# instaspin_bldc_driver.net
KiCad netlist of a schematic drawn in Altium Designer
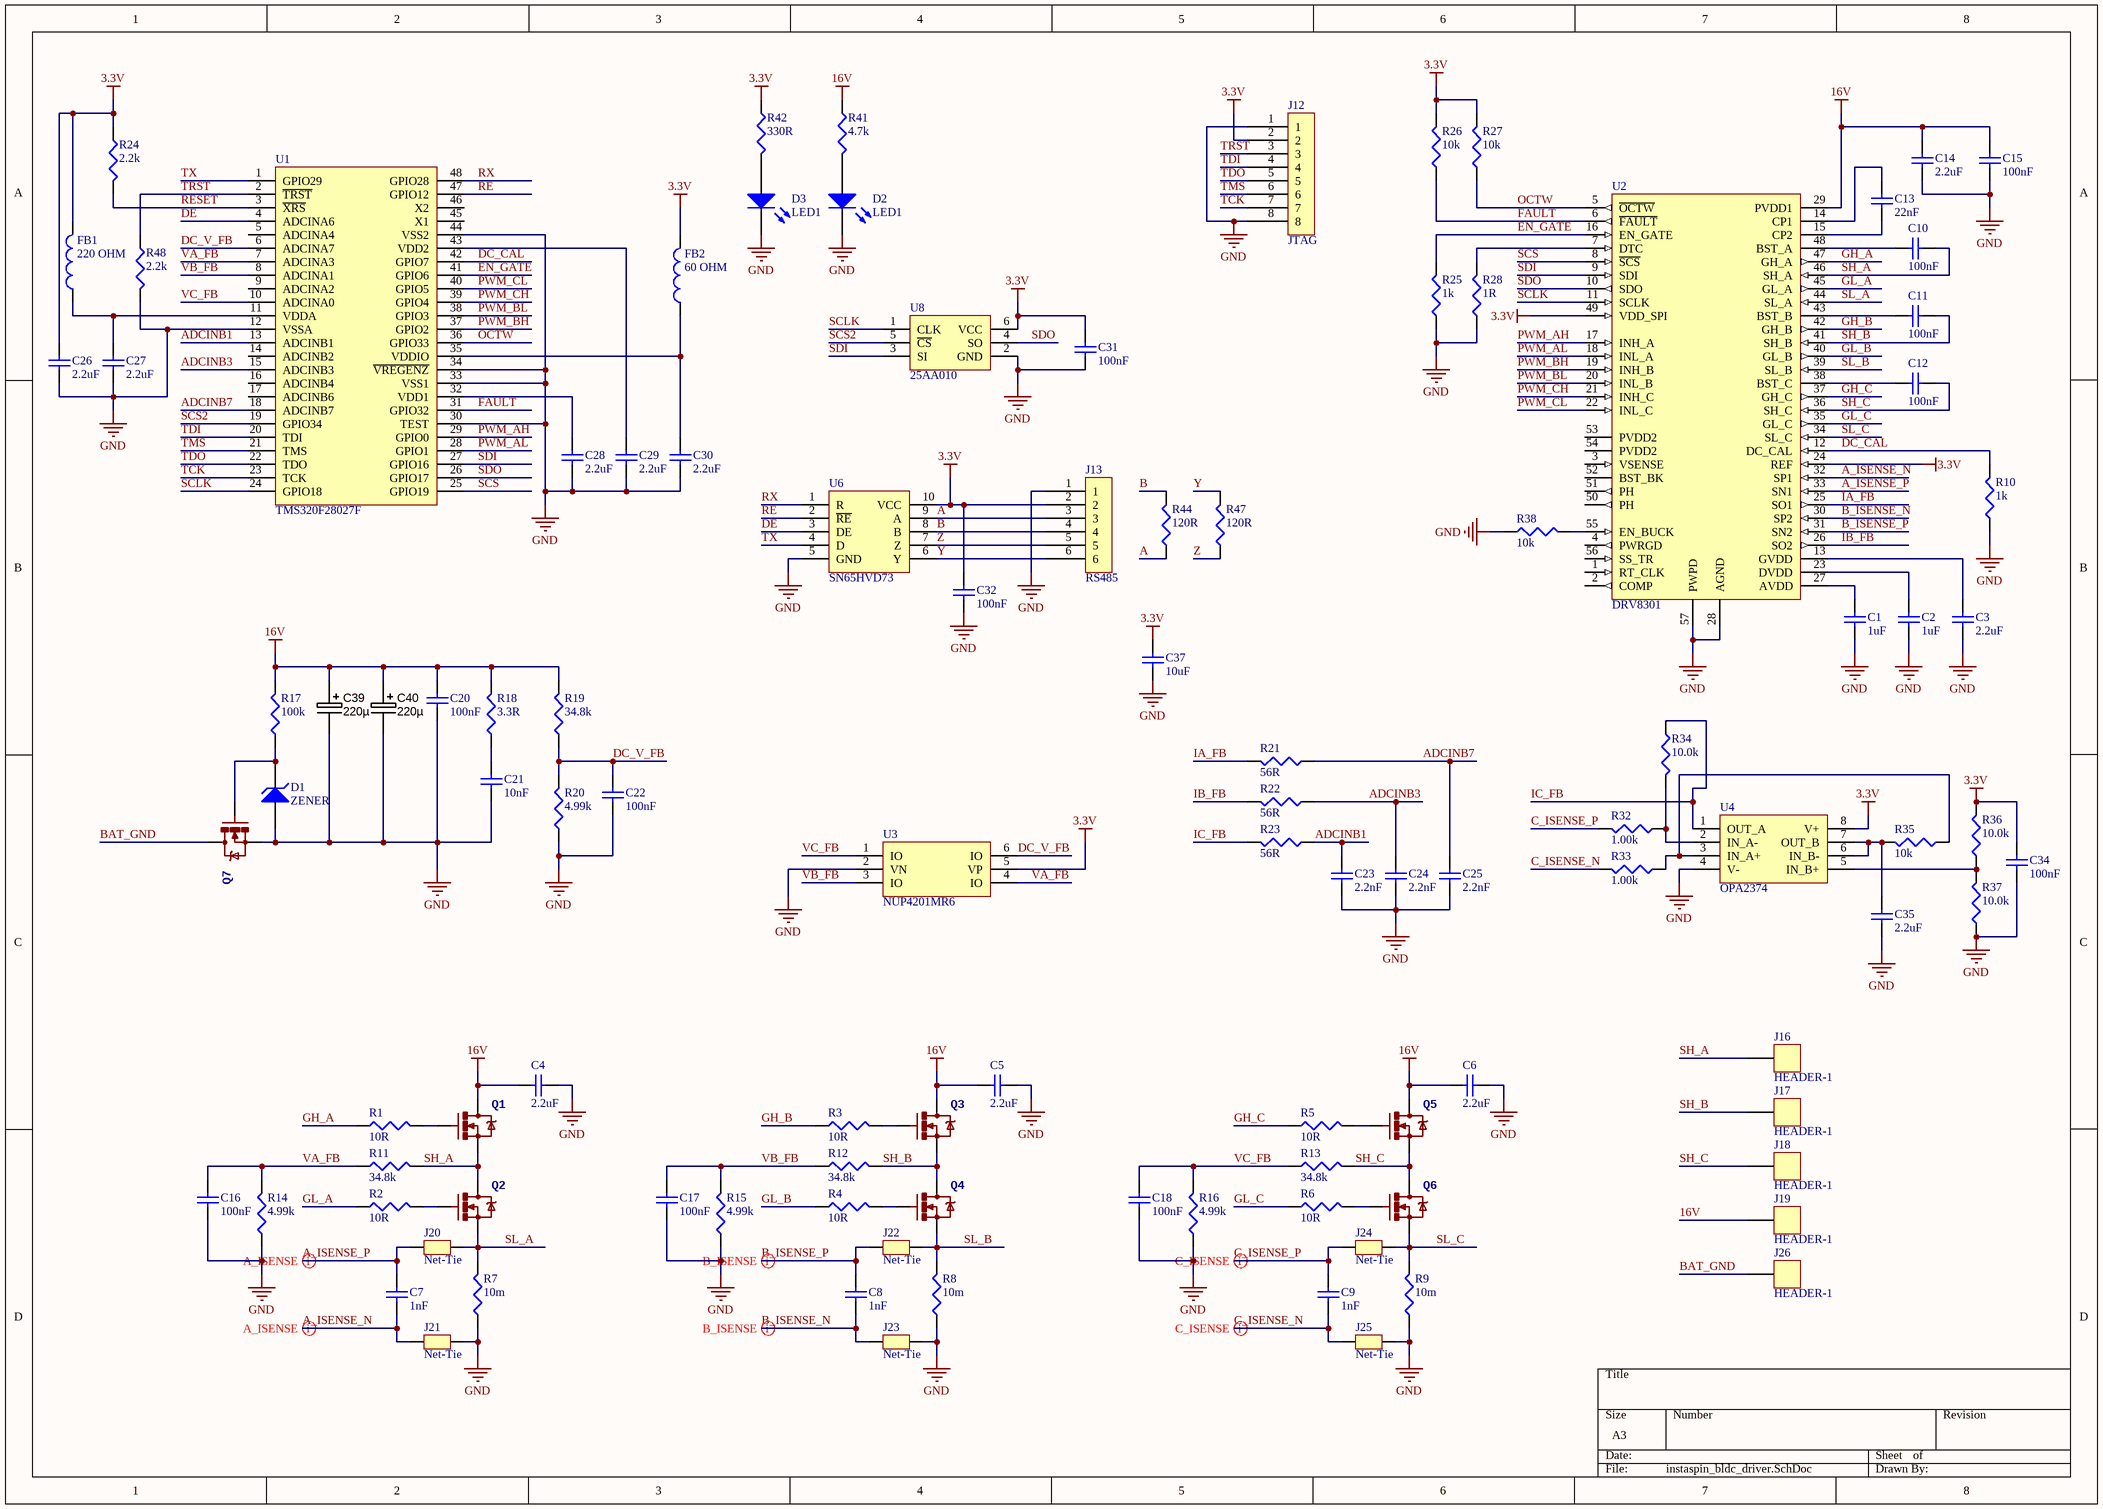
[diagram p0: instaspin_bldc_driver.SchDoc]

(export (version "E")
  (design (tool "Eeschema 10.0.6"))
  (components
    (comp (ref "C1")
      (value "1uF")
      (footprint "1608[0603]")
      (description "Capacitor (Semiconductor SIM Model)")
      (fields (field (name "PUBLISHER") "Altium Limited"))
      (libsource (lib "Miscellaneous Devices") (part "Cap Semi"))
    )
    (comp (ref "C2")
      (value "1uF")
      (footprint "1608[0603]")
      (description "Capacitor (Semiconductor SIM Model)")
      (fields (field (name "PUBLISHER") "Altium Limited"))
      (libsource (lib "Miscellaneous Devices") (part "Cap Semi"))
    )
    (comp (ref "C3")
      (value "2.2uF")
      (footprint "1608[0603]")
      (description "Capacitor (Semiconductor SIM Model)")
      (fields (field (name "PUBLISHER") "Altium Limited"))
      (libsource (lib "Miscellaneous Devices") (part "Cap Semi"))
    )
    (comp (ref "C4")
      (value "2.2uF")
      (footprint "C1206")
      (description "Capacitor (Semiconductor SIM Model)")
      (fields (field (name "PUBLISHER") "Altium Limited"))
      (libsource (lib "Miscellaneous Devices") (part "Cap Semi"))
    )
    (comp (ref "C5")
      (value "2.2uF")
      (footprint "C1206")
      (description "Capacitor (Semiconductor SIM Model)")
      (fields (field (name "PUBLISHER") "Altium Limited"))
      (libsource (lib "Miscellaneous Devices") (part "Cap Semi"))
    )
    (comp (ref "C6")
      (value "2.2uF")
      (footprint "C1206")
      (description "Capacitor (Semiconductor SIM Model)")
      (fields (field (name "PUBLISHER") "Altium Limited"))
      (libsource (lib "Miscellaneous Devices") (part "Cap Semi"))
    )
    (comp (ref "C7")
      (value "1nF")
      (footprint "1608[0603]")
      (description "Capacitor (Semiconductor SIM Model)")
      (fields (field (name "PUBLISHER") "Altium Limited"))
      (libsource (lib "Miscellaneous Devices") (part "Cap Semi"))
    )
    (comp (ref "C8")
      (value "1nF")
      (footprint "1608[0603]")
      (description "Capacitor (Semiconductor SIM Model)")
      (fields (field (name "PUBLISHER") "Altium Limited"))
      (libsource (lib "Miscellaneous Devices") (part "Cap Semi"))
    )
    (comp (ref "C9")
      (value "1nF")
      (footprint "1608[0603]")
      (description "Capacitor (Semiconductor SIM Model)")
      (fields (field (name "PUBLISHER") "Altium Limited"))
      (libsource (lib "Miscellaneous Devices") (part "Cap Semi"))
    )
    (comp (ref "C10")
      (value "100nF")
      (footprint "1608[0603]")
      (description "Capacitor (Semiconductor SIM Model)")
      (fields (field (name "PUBLISHER") "Altium Limited"))
      (libsource (lib "Miscellaneous Devices") (part "Cap Semi"))
    )
    (comp (ref "C11")
      (value "100nF")
      (footprint "1608[0603]")
      (description "Capacitor (Semiconductor SIM Model)")
      (fields (field (name "PUBLISHER") "Altium Limited"))
      (libsource (lib "Miscellaneous Devices") (part "Cap Semi"))
    )
    (comp (ref "C12")
      (value "100nF")
      (footprint "1608[0603]")
      (description "Capacitor (Semiconductor SIM Model)")
      (fields (field (name "PUBLISHER") "Altium Limited"))
      (libsource (lib "Miscellaneous Devices") (part "Cap Semi"))
    )
    (comp (ref "C13")
      (value "22nF")
      (footprint "1608[0603]")
      (description "Capacitor (Semiconductor SIM Model)")
      (fields (field (name "PUBLISHER") "Altium Limited"))
      (libsource (lib "Miscellaneous Devices") (part "Cap Semi"))
    )
    (comp (ref "C14")
      (value "2.2uF")
      (footprint "C1206")
      (description "Capacitor (Semiconductor SIM Model)")
      (fields (field (name "PUBLISHER") "Altium Limited"))
      (libsource (lib "Miscellaneous Devices") (part "Cap Semi"))
    )
    (comp (ref "C15")
      (value "100nF")
      (footprint "1608[0603]")
      (description "Capacitor (Semiconductor SIM Model)")
      (fields (field (name "PUBLISHER") "Altium Limited"))
      (libsource (lib "Miscellaneous Devices") (part "Cap Semi"))
    )
    (comp (ref "C16")
      (value "100nF")
      (footprint "1608[0603]")
      (description "Capacitor (Semiconductor SIM Model)")
      (fields (field (name "PUBLISHER") "Altium Limited"))
      (libsource (lib "Miscellaneous Devices") (part "Cap Semi"))
    )
    (comp (ref "C17")
      (value "100nF")
      (footprint "1608[0603]")
      (description "Capacitor (Semiconductor SIM Model)")
      (fields (field (name "PUBLISHER") "Altium Limited"))
      (libsource (lib "Miscellaneous Devices") (part "Cap Semi"))
    )
    (comp (ref "C18")
      (value "100nF")
      (footprint "1608[0603]")
      (description "Capacitor (Semiconductor SIM Model)")
      (fields (field (name "PUBLISHER") "Altium Limited"))
      (libsource (lib "Miscellaneous Devices") (part "Cap Semi"))
    )
    (comp (ref "C20")
      (value "100nF")
      (footprint "1608[0603]")
      (description "Capacitor (Semiconductor SIM Model)")
      (fields (field (name "PUBLISHER") "Altium Limited"))
      (libsource (lib "Miscellaneous Devices") (part "Cap Semi"))
    )
    (comp (ref "C21")
      (value "10nF")
      (footprint "1608[0603]")
      (description "Capacitor (Semiconductor SIM Model)")
      (fields (field (name "PUBLISHER") "Altium Limited"))
      (libsource (lib "Miscellaneous Devices") (part "Cap Semi"))
    )
    (comp (ref "C22")
      (value "100nF")
      (footprint "1608[0603]")
      (description "Capacitor (Semiconductor SIM Model)")
      (fields (field (name "PUBLISHER") "Altium Limited"))
      (libsource (lib "Miscellaneous Devices") (part "Cap Semi"))
    )
    (comp (ref "C23")
      (value "2.2nF")
      (footprint "1608[0603]")
      (description "Capacitor (Semiconductor SIM Model)")
      (fields (field (name "PUBLISHER") "Altium Limited"))
      (libsource (lib "Miscellaneous Devices") (part "Cap Semi"))
    )
    (comp (ref "C24")
      (value "2.2nF")
      (footprint "1608[0603]")
      (description "Capacitor (Semiconductor SIM Model)")
      (fields (field (name "PUBLISHER") "Altium Limited"))
      (libsource (lib "Miscellaneous Devices") (part "Cap Semi"))
    )
    (comp (ref "C25")
      (value "2.2nF")
      (footprint "1608[0603]")
      (description "Capacitor (Semiconductor SIM Model)")
      (fields (field (name "PUBLISHER") "Altium Limited"))
      (libsource (lib "Miscellaneous Devices") (part "Cap Semi"))
    )
    (comp (ref "C26")
      (value "2.2uF")
      (footprint "1608[0603]")
      (description "Capacitor (Semiconductor SIM Model)")
      (fields (field (name "PUBLISHER") "Altium Limited"))
      (libsource (lib "Miscellaneous Devices") (part "Cap Semi"))
    )
    (comp (ref "C27")
      (value "2.2uF")
      (footprint "1608[0603]")
      (description "Capacitor (Semiconductor SIM Model)")
      (fields (field (name "PUBLISHER") "Altium Limited"))
      (libsource (lib "Miscellaneous Devices") (part "Cap Semi"))
    )
    (comp (ref "C28")
      (value "2.2uF")
      (footprint "1608[0603]")
      (description "Capacitor (Semiconductor SIM Model)")
      (fields (field (name "PUBLISHER") "Altium Limited"))
      (libsource (lib "Miscellaneous Devices") (part "Cap Semi"))
    )
    (comp (ref "C29")
      (value "2.2uF")
      (footprint "1608[0603]")
      (description "Capacitor (Semiconductor SIM Model)")
      (fields (field (name "PUBLISHER") "Altium Limited"))
      (libsource (lib "Miscellaneous Devices") (part "Cap Semi"))
    )
    (comp (ref "C30")
      (value "2.2uF")
      (footprint "1608[0603]")
      (description "Capacitor (Semiconductor SIM Model)")
      (fields (field (name "PUBLISHER") "Altium Limited"))
      (libsource (lib "Miscellaneous Devices") (part "Cap Semi"))
    )
    (comp (ref "C31")
      (value "100nF")
      (footprint "1608[0603]")
      (description "Capacitor (Semiconductor SIM Model)")
      (fields (field (name "PUBLISHER") "Altium Limited"))
      (libsource (lib "Miscellaneous Devices") (part "Cap Semi"))
    )
    (comp (ref "C32")
      (value "100nF")
      (footprint "1608[0603]")
      (description "Capacitor (Semiconductor SIM Model)")
      (fields (field (name "PUBLISHER") "Altium Limited"))
      (libsource (lib "Miscellaneous Devices") (part "Cap Semi"))
    )
    (comp (ref "C34")
      (value "100nF")
      (footprint "1608[0603]")
      (description "Capacitor (Semiconductor SIM Model)")
      (fields (field (name "PUBLISHER") "Altium Limited"))
      (libsource (lib "Miscellaneous Devices") (part "Cap Semi"))
    )
    (comp (ref "C35")
      (value "2.2uF")
      (footprint "1608[0603]")
      (description "Capacitor (Semiconductor SIM Model)")
      (fields (field (name "PUBLISHER") "Altium Limited"))
      (libsource (lib "Miscellaneous Devices") (part "Cap Semi"))
    )
    (comp (ref "C37")
      (value "10uF")
      (footprint "C1206")
      (description "Capacitor (Semiconductor SIM Model)")
      (fields (field (name "PUBLISHER") "Altium Limited"))
      (libsource (lib "Miscellaneous Devices") (part "Cap Semi"))
    )
    (comp (ref "C39")
      (value "220µ")
      (footprint "CAP_ELEC_6.3x4.2")
      (description "Capacitor THT Alum Elec 470uF 20% 16V")
      (fields (field (name "TOLERANCE") "±20%"))
      (libsource (lib "PBL - Capacitors") (part "CAPE_470u_16V_THT"))
    )
    (comp (ref "C40")
      (value "220µ")
      (footprint "CAP_ELEC_6.3x4.2")
      (description "Capacitor THT Alum Elec 470uF 20% 16V")
      (fields (field (name "TOLERANCE") "±20%"))
      (libsource (lib "PBL - Capacitors") (part "CAPE_470u_16V_THT"))
    )
    (comp (ref "D1")
      (value "ZENER")
      (footprint "SODFL370X135-2N")
      (libsource (lib "power") (part "ZENER-DIODE"))
    )
    (comp (ref "D2")
      (value "LED1")
      (footprint "1608[0603]")
      (description "Typical RED GaAs LED")
      (fields (field (name "PUBLISHER") "Altium Limited"))
      (libsource (lib "Miscellaneous Devices") (part "LED1"))
    )
    (comp (ref "D3")
      (value "LED1")
      (footprint "1608[0603]")
      (description "Typical RED GaAs LED")
      (fields (field (name "PUBLISHER") "Altium Limited"))
      (libsource (lib "Miscellaneous Devices") (part "LED1"))
    )
    (comp (ref "FB1")
      (value "220 OHM")
      (footprint "INDC1608L")
      (description "Ferrite")
      (fields (field (name "PUBLISHER") "Altium Limited"))
      (libsource (lib "Miscellaneous Devices") (part "Inductor"))
    )
    (comp (ref "FB2")
      (value "60 OHM")
      (footprint "INDC1608L")
      (description "Ferrite")
      (fields (field (name "PUBLISHER") "Altium Limited"))
      (libsource (lib "Miscellaneous Devices") (part "Inductor"))
    )
    (comp (ref "J12")
      (value "JTAG")
      (footprint "MICRO-MATCH-8")
      (libsource (lib "connectors") (part "HEADER-8"))
    )
    (comp (ref "J13")
      (value "RS485")
      (footprint "MICRO-MATCH-6")
      (libsource (lib "connectors") (part "HEADER-6"))
    )
    (comp (ref "J16")
      (value "HEADER-1")
      (footprint "2MM-BANANA-SOCKET")
      (libsource (lib "connectors") (part "HEADER-1"))
    )
    (comp (ref "J17")
      (value "HEADER-1")
      (footprint "2MM-BANANA-SOCKET")
      (libsource (lib "connectors") (part "HEADER-1"))
    )
    (comp (ref "J18")
      (value "HEADER-1")
      (footprint "2MM-BANANA-SOCKET")
      (libsource (lib "connectors") (part "HEADER-1"))
    )
    (comp (ref "J19")
      (value "HEADER-1")
      (footprint "2MM-BANANA-SOCKET")
      (libsource (lib "connectors") (part "HEADER-1"))
    )
    (comp (ref "J20")
      (value "Net-Tie")
      (footprint "NET-TIE-0803")
      (libsource (lib "connectors") (part "Net-Tie"))
    )
    (comp (ref "J21")
      (value "Net-Tie")
      (footprint "NET-TIE-0803")
      (libsource (lib "connectors") (part "Net-Tie"))
    )
    (comp (ref "J22")
      (value "Net-Tie")
      (footprint "NET-TIE-0803")
      (libsource (lib "connectors") (part "Net-Tie"))
    )
    (comp (ref "J23")
      (value "Net-Tie")
      (footprint "NET-TIE-0803")
      (libsource (lib "connectors") (part "Net-Tie"))
    )
    (comp (ref "J24")
      (value "Net-Tie")
      (footprint "NET-TIE-0803")
      (libsource (lib "connectors") (part "Net-Tie"))
    )
    (comp (ref "J25")
      (value "Net-Tie")
      (footprint "NET-TIE-0803")
      (libsource (lib "connectors") (part "Net-Tie"))
    )
    (comp (ref "J26")
      (value "HEADER-1")
      (footprint "2MM-BANANA-SOCKET")
      (libsource (lib "connectors") (part "HEADER-1"))
    )
    (comp (ref "Q1") (value "MOSFET-N") (footprint "SOT669") (libsource (lib "mosfets") (part "MOSFET-N")))
    (comp (ref "Q2") (value "MOSFET-N") (footprint "SOT669") (libsource (lib "mosfets") (part "MOSFET-N")))
    (comp (ref "Q3") (value "MOSFET-N") (footprint "SOT669") (libsource (lib "mosfets") (part "MOSFET-N")))
    (comp (ref "Q4") (value "MOSFET-N") (footprint "SOT669") (libsource (lib "mosfets") (part "MOSFET-N")))
    (comp (ref "Q5") (value "MOSFET-N") (footprint "SOT669") (libsource (lib "mosfets") (part "MOSFET-N")))
    (comp (ref "Q6") (value "MOSFET-N") (footprint "SOT669") (libsource (lib "mosfets") (part "MOSFET-N")))
    (comp (ref "Q7") (value "MOSFET-N") (footprint "SOT669") (libsource (lib "") (part "MOSFET-N_1")))
    (comp (ref "R1")
      (value "10R")
      (footprint "J1-0603")
      (description "Resistor")
      (fields (field (name "PUBLISHER") "Altium Limited"))
      (libsource (lib "Miscellaneous Devices") (part "Res3"))
    )
    (comp (ref "R2")
      (value "10R")
      (footprint "J1-0603")
      (description "Resistor")
      (fields (field (name "PUBLISHER") "Altium Limited"))
      (libsource (lib "Miscellaneous Devices") (part "Res3"))
    )
    (comp (ref "R3")
      (value "10R")
      (footprint "J1-0603")
      (description "Resistor")
      (fields (field (name "PUBLISHER") "Altium Limited"))
      (libsource (lib "Miscellaneous Devices") (part "Res3"))
    )
    (comp (ref "R4")
      (value "10R")
      (footprint "J1-0603")
      (description "Resistor")
      (fields (field (name "PUBLISHER") "Altium Limited"))
      (libsource (lib "Miscellaneous Devices") (part "Res3"))
    )
    (comp (ref "R5")
      (value "10R")
      (footprint "J1-0603")
      (description "Resistor")
      (fields (field (name "PUBLISHER") "Altium Limited"))
      (libsource (lib "Miscellaneous Devices") (part "Res3"))
    )
    (comp (ref "R6")
      (value "10R")
      (footprint "J1-0603")
      (description "Resistor")
      (fields (field (name "PUBLISHER") "Altium Limited"))
      (libsource (lib "Miscellaneous Devices") (part "Res3"))
    )
    (comp (ref "R7")
      (value "10m")
      (footprint "2512M")
      (description "Resistor")
      (fields (field (name "PUBLISHER") "Altium Limited"))
      (libsource (lib "Miscellaneous Devices") (part "Res3"))
    )
    (comp (ref "R8")
      (value "10m")
      (footprint "2512M")
      (description "Resistor")
      (fields (field (name "PUBLISHER") "Altium Limited"))
      (libsource (lib "Miscellaneous Devices") (part "Res3"))
    )
    (comp (ref "R9")
      (value "10m")
      (footprint "2512M")
      (description "Resistor")
      (fields (field (name "PUBLISHER") "Altium Limited"))
      (libsource (lib "Miscellaneous Devices") (part "Res3"))
    )
    (comp (ref "R10")
      (value "1k")
      (footprint "J1-0603")
      (description "Resistor")
      (fields (field (name "PUBLISHER") "Altium Limited"))
      (libsource (lib "Miscellaneous Devices") (part "Res3"))
    )
    (comp (ref "R11")
      (value "34.8k")
      (footprint "J1-0603")
      (description "Resistor")
      (fields (field (name "PUBLISHER") "Altium Limited"))
      (libsource (lib "Miscellaneous Devices") (part "Res3"))
    )
    (comp (ref "R12")
      (value "34.8k")
      (footprint "J1-0603")
      (description "Resistor")
      (fields (field (name "PUBLISHER") "Altium Limited"))
      (libsource (lib "Miscellaneous Devices") (part "Res3"))
    )
    (comp (ref "R13")
      (value "34.8k")
      (footprint "J1-0603")
      (description "Resistor")
      (fields (field (name "PUBLISHER") "Altium Limited"))
      (libsource (lib "Miscellaneous Devices") (part "Res3"))
    )
    (comp (ref "R14")
      (value "4.99k")
      (footprint "J1-0603")
      (description "Resistor")
      (fields (field (name "PUBLISHER") "Altium Limited"))
      (libsource (lib "Miscellaneous Devices") (part "Res3"))
    )
    (comp (ref "R15")
      (value "4.99k")
      (footprint "J1-0603")
      (description "Resistor")
      (fields (field (name "PUBLISHER") "Altium Limited"))
      (libsource (lib "Miscellaneous Devices") (part "Res3"))
    )
    (comp (ref "R16")
      (value "4.99k")
      (footprint "J1-0603")
      (description "Resistor")
      (fields (field (name "PUBLISHER") "Altium Limited"))
      (libsource (lib "Miscellaneous Devices") (part "Res3"))
    )
    (comp (ref "R17")
      (value "100k")
      (footprint "J1-0603")
      (description "Resistor")
      (fields (field (name "PUBLISHER") "Altium Limited"))
      (libsource (lib "Miscellaneous Devices") (part "Res3"))
    )
    (comp (ref "R18")
      (value "3.3R")
      (footprint "C1206")
      (description "Resistor")
      (fields (field (name "PUBLISHER") "Altium Limited"))
      (libsource (lib "Miscellaneous Devices") (part "Res3"))
    )
    (comp (ref "R19")
      (value "34.8k")
      (footprint "J1-0603")
      (description "Resistor")
      (fields (field (name "PUBLISHER") "Altium Limited"))
      (libsource (lib "Miscellaneous Devices") (part "Res3"))
    )
    (comp (ref "R20")
      (value "4.99k")
      (footprint "J1-0603")
      (description "Resistor")
      (fields (field (name "PUBLISHER") "Altium Limited"))
      (libsource (lib "Miscellaneous Devices") (part "Res3"))
    )
    (comp (ref "R21")
      (value "56R")
      (footprint "J1-0603")
      (description "Resistor")
      (fields (field (name "PUBLISHER") "Altium Limited"))
      (libsource (lib "Miscellaneous Devices") (part "Res3"))
    )
    (comp (ref "R22")
      (value "56R")
      (footprint "J1-0603")
      (description "Resistor")
      (fields (field (name "PUBLISHER") "Altium Limited"))
      (libsource (lib "Miscellaneous Devices") (part "Res3"))
    )
    (comp (ref "R23")
      (value "56R")
      (footprint "J1-0603")
      (description "Resistor")
      (fields (field (name "PUBLISHER") "Altium Limited"))
      (libsource (lib "Miscellaneous Devices") (part "Res3"))
    )
    (comp (ref "R24")
      (value "2.2k")
      (footprint "J1-0603")
      (description "Resistor")
      (fields (field (name "PUBLISHER") "Altium Limited"))
      (libsource (lib "Miscellaneous Devices") (part "Res3"))
    )
    (comp (ref "R25")
      (value "1k")
      (footprint "J1-0603")
      (description "Resistor")
      (fields (field (name "PUBLISHER") "Altium Limited"))
      (libsource (lib "Miscellaneous Devices") (part "Res3"))
    )
    (comp (ref "R26")
      (value "10k")
      (footprint "J1-0603")
      (description "Resistor")
      (fields (field (name "PUBLISHER") "Altium Limited"))
      (libsource (lib "Miscellaneous Devices") (part "Res3"))
    )
    (comp (ref "R27")
      (value "10k")
      (footprint "J1-0603")
      (description "Resistor")
      (fields (field (name "PUBLISHER") "Altium Limited"))
      (libsource (lib "Miscellaneous Devices") (part "Res3"))
    )
    (comp (ref "R28")
      (value "1R")
      (footprint "J1-0603")
      (description "Resistor")
      (fields (field (name "PUBLISHER") "Altium Limited"))
      (libsource (lib "Miscellaneous Devices") (part "Res3"))
    )
    (comp (ref "R32")
      (value "1.00k")
      (footprint "J1-0603")
      (description "Resistor")
      (fields (field (name "PUBLISHER") "Altium Limited"))
      (libsource (lib "Miscellaneous Devices") (part "Res3"))
    )
    (comp (ref "R33")
      (value "1.00k")
      (footprint "J1-0603")
      (description "Resistor")
      (fields (field (name "PUBLISHER") "Altium Limited"))
      (libsource (lib "Miscellaneous Devices") (part "Res3"))
    )
    (comp (ref "R34")
      (value "10.0k")
      (footprint "J1-0603")
      (description "Resistor")
      (fields (field (name "PUBLISHER") "Altium Limited"))
      (libsource (lib "Miscellaneous Devices") (part "Res3"))
    )
    (comp (ref "R35")
      (value "10k")
      (footprint "J1-0603")
      (description "Resistor")
      (fields (field (name "PUBLISHER") "Altium Limited"))
      (libsource (lib "Miscellaneous Devices") (part "Res3"))
    )
    (comp (ref "R36")
      (value "10.0k")
      (footprint "J1-0603")
      (description "Resistor")
      (fields (field (name "PUBLISHER") "Altium Limited"))
      (libsource (lib "Miscellaneous Devices") (part "Res3"))
    )
    (comp (ref "R37")
      (value "10.0k")
      (footprint "J1-0603")
      (description "Resistor")
      (fields (field (name "PUBLISHER") "Altium Limited"))
      (libsource (lib "Miscellaneous Devices") (part "Res3"))
    )
    (comp (ref "R38")
      (value "10k")
      (footprint "J1-0603")
      (description "Resistor")
      (fields (field (name "PUBLISHER") "Altium Limited"))
      (libsource (lib "Miscellaneous Devices") (part "Res3"))
    )
    (comp (ref "R41")
      (value "4.7k")
      (footprint "J1-0603")
      (description "Resistor")
      (fields (field (name "PUBLISHER") "Altium Limited"))
      (libsource (lib "Miscellaneous Devices") (part "Res3"))
    )
    (comp (ref "R42")
      (value "330R")
      (footprint "J1-0603")
      (description "Resistor")
      (fields (field (name "PUBLISHER") "Altium Limited"))
      (libsource (lib "Miscellaneous Devices") (part "Res3"))
    )
    (comp (ref "R44")
      (value "120R")
      (footprint "J1-0603")
      (description "Resistor")
      (fields (field (name "PUBLISHER") "Altium Limited"))
      (libsource (lib "Miscellaneous Devices") (part "Res3"))
    )
    (comp (ref "R47")
      (value "120R")
      (footprint "J1-0603")
      (description "Resistor")
      (fields (field (name "PUBLISHER") "Altium Limited"))
      (libsource (lib "Miscellaneous Devices") (part "Res3"))
    )
    (comp (ref "R48")
      (value "2.2k")
      (footprint "J1-0603")
      (description "Resistor")
      (fields (field (name "PUBLISHER") "Altium Limited"))
      (libsource (lib "Miscellaneous Devices") (part "Res3"))
    )
    (comp (ref "U1")
      (value "TMS320F28027F")
      (footprint "PQFP48")
      (libsource (lib "texas_instruments") (part "TMS320F28027F"))
    )
    (comp (ref "U2")
      (value "DRV8301")
      (footprint "SO56_POWERPAD")
      (libsource (lib "texas_instruments") (part "DRV8301"))
    )
    (comp (ref "U3")
      (value "NUP4201MR6")
      (footprint "TSOP-6")
      (libsource (lib "digital") (part "NUP4201MR6"))
    )
    (comp (ref "U4")
      (value "OPA2374")
      (footprint "SOT23-8")
      (libsource (lib "texas_instruments") (part "OPA2374"))
    )
    (comp (ref "U6")
      (value "SN65HVD73")
      (footprint "SOP10")
      (libsource (lib "texas_instruments") (part "SN65HVD3086E"))
    )
    (comp (ref "U8")
      (value "25AA010")
      (footprint "TSOT-23-6")
      (description "EEPROM")
      (libsource (lib "digital") (part "25AA010"))
    )
  )
  (nets
    (net (code "1") (name "/A") (class "Default")
      (node (ref "J13") (pin "3") (pinfunction "3_3") (pintype "passive"))
      (node (ref "R44") (pin "1") (pinfunction "1_1") (pintype "passive"))
      (node (ref "U6") (pin "9") (pinfunction "A_9") (pintype "passive"))
    )
    (net (code "2") (name "/ADCINB1") (class "Default")
      (node (ref "C23") (pin "2") (pinfunction "2_2") (pintype "passive"))
      (node (ref "R23") (pin "1") (pinfunction "1_1") (pintype "passive"))
      (node (ref "U1") (pin "13") (pinfunction "ADCINB1_13") (pintype "passive"))
    )
    (net (code "3") (name "/ADCINB3") (class "Default")
      (node (ref "C24") (pin "2") (pinfunction "2_2") (pintype "passive"))
      (node (ref "R22") (pin "1") (pinfunction "1_1") (pintype "passive"))
      (node (ref "U1") (pin "15") (pinfunction "ADCINB3_15") (pintype "passive"))
    )
    (net (code "4") (name "/ADCINB7") (class "Default")
      (node (ref "C25") (pin "2") (pinfunction "2_2") (pintype "passive"))
      (node (ref "R21") (pin "1") (pinfunction "1_1") (pintype "passive"))
      (node (ref "U1") (pin "18") (pinfunction "ADCINB7_18") (pintype "passive"))
    )
    (net (code "5") (name "/A_ISENSE_N") (class "Default")
      (node (ref "C7") (pin "1") (pinfunction "1_1") (pintype "passive"))
      (node (ref "J21") (pin "1") (pinfunction "1_1") (pintype "passive"))
      (node (ref "U2") (pin "32") (pinfunction "SP1_32") (pintype "input"))
    )
    (net (code "6") (name "/A_ISENSE_P") (class "Default")
      (node (ref "C7") (pin "2") (pinfunction "2_2") (pintype "passive"))
      (node (ref "J20") (pin "1") (pinfunction "1_1") (pintype "passive"))
      (node (ref "U2") (pin "33") (pinfunction "SN1_33") (pintype "input"))
    )
    (net (code "7") (name "/B") (class "Default")
      (node (ref "J13") (pin "4") (pinfunction "4_4") (pintype "passive"))
      (node (ref "R44") (pin "2") (pinfunction "2_2") (pintype "passive"))
      (node (ref "U6") (pin "8") (pinfunction "B_8") (pintype "passive"))
    )
    (net (code "8") (name "/BAT_GND") (class "Default")
      (node (ref "J26") (pin "1") (pinfunction "1_1") (pintype "passive"))
      (node (ref "Q7") (pin "D") (pinfunction "D_D") (pintype "passive"))
    )
    (net (code "9") (name "/B_ISENSE_N") (class "Default")
      (node (ref "C8") (pin "1") (pinfunction "1_1") (pintype "passive"))
      (node (ref "J23") (pin "1") (pinfunction "1_1") (pintype "passive"))
      (node (ref "U2") (pin "30") (pinfunction "SP2_30") (pintype "input"))
    )
    (net (code "10") (name "/B_ISENSE_P") (class "Default")
      (node (ref "C8") (pin "2") (pinfunction "2_2") (pintype "passive"))
      (node (ref "J22") (pin "1") (pinfunction "1_1") (pintype "passive"))
      (node (ref "U2") (pin "31") (pinfunction "SN2_31") (pintype "input"))
    )
    (net (code "11") (name "/C_ISENSE_N") (class "Default")
      (node (ref "C9") (pin "1") (pinfunction "1_1") (pintype "passive"))
      (node (ref "J25") (pin "1") (pinfunction "1_1") (pintype "passive"))
      (node (ref "R33") (pin "2") (pinfunction "2_2") (pintype "passive"))
    )
    (net (code "12") (name "/C_ISENSE_P") (class "Default")
      (node (ref "C9") (pin "2") (pinfunction "2_2") (pintype "passive"))
      (node (ref "J24") (pin "1") (pinfunction "1_1") (pintype "passive"))
      (node (ref "R32") (pin "2") (pinfunction "2_2") (pintype "passive"))
    )
    (net (code "13") (name "/DC_CAL") (class "Default")
      (node (ref "R10") (pin "2") (pinfunction "2_2") (pintype "passive"))
      (node (ref "U1") (pin "42") (pinfunction "GPIO7_42") (pintype "passive"))
      (node (ref "U2") (pin "12") (pinfunction "DC_CAL_12") (pintype "input"))
    )
    (net (code "14") (name "/DC_V_FB") (class "Default")
      (node (ref "C22") (pin "2") (pinfunction "2_2") (pintype "passive"))
      (node (ref "R19") (pin "1") (pinfunction "1_1") (pintype "passive"))
      (node (ref "R20") (pin "2") (pinfunction "2_2") (pintype "passive"))
      (node (ref "U1") (pin "6") (pinfunction "ADCINA7_6") (pintype "passive"))
      (node (ref "U3") (pin "6") (pinfunction "IO_6") (pintype "passive"))
    )
    (net (code "15") (name "/DE") (class "Default")
      (node (ref "U1") (pin "4") (pinfunction "ADCINA6_4") (pintype "passive"))
      (node (ref "U6") (pin "3") (pinfunction "DE_3") (pintype "passive"))
    )
    (net (code "16") (name "/EN_GATE") (class "Default")
      (node (ref "R25") (pin "2") (pinfunction "2_2") (pintype "passive"))
      (node (ref "U1") (pin "41") (pinfunction "GPIO6_41") (pintype "passive"))
      (node (ref "U2") (pin "16") (pinfunction "EN_GATE_16") (pintype "input"))
    )
    (net (code "17") (name "/FAULT") (class "Default")
      (node (ref "R26") (pin "1") (pinfunction "1_1") (pintype "passive"))
      (node (ref "U1") (pin "31") (pinfunction "GPIO32_31") (pintype "passive"))
      (node (ref "U2") (pin "6") (pinfunction "~{FAULT}_6") (pintype "output"))
    )
    (net (code "18") (name "/GH_A") (class "Default")
      (node (ref "R1") (pin "1") (pinfunction "1_1") (pintype "passive"))
      (node (ref "U2") (pin "47") (pinfunction "GH_A_47") (pintype "output"))
    )
    (net (code "19") (name "/GH_B") (class "Default")
      (node (ref "R3") (pin "1") (pinfunction "1_1") (pintype "passive"))
      (node (ref "U2") (pin "42") (pinfunction "GH_B_42") (pintype "output"))
    )
    (net (code "20") (name "/GH_C") (class "Default")
      (node (ref "R5") (pin "1") (pinfunction "1_1") (pintype "passive"))
      (node (ref "U2") (pin "37") (pinfunction "GH_C_37") (pintype "output"))
    )
    (net (code "21") (name "/GL_A") (class "Default")
      (node (ref "R2") (pin "1") (pinfunction "1_1") (pintype "passive"))
      (node (ref "U2") (pin "45") (pinfunction "GL_A_45") (pintype "output"))
    )
    (net (code "22") (name "/GL_B") (class "Default")
      (node (ref "R4") (pin "1") (pinfunction "1_1") (pintype "passive"))
      (node (ref "U2") (pin "40") (pinfunction "GL_B_40") (pintype "output"))
    )
    (net (code "23") (name "/GL_C") (class "Default")
      (node (ref "R6") (pin "1") (pinfunction "1_1") (pintype "passive"))
      (node (ref "U2") (pin "35") (pinfunction "GL_C_35") (pintype "output"))
    )
    (net (code "24") (name "/IA_FB") (class "Default")
      (node (ref "R21") (pin "2") (pinfunction "2_2") (pintype "passive"))
      (node (ref "U2") (pin "25") (pinfunction "SO1_25") (pintype "output"))
    )
    (net (code "25") (name "/IB_FB") (class "Default")
      (node (ref "R22") (pin "2") (pinfunction "2_2") (pintype "passive"))
      (node (ref "U2") (pin "26") (pinfunction "SO2_26") (pintype "output"))
    )
    (net (code "26") (name "/IC_FB") (class "Default")
      (node (ref "R23") (pin "2") (pinfunction "2_2") (pintype "passive"))
      (node (ref "R34") (pin "1") (pinfunction "1_1") (pintype "passive"))
      (node (ref "U4") (pin "1") (pinfunction "OUT_A_1") (pintype "passive"))
    )
    (net (code "27") (name "/OCTW") (class "Default")
      (node (ref "R27") (pin "1") (pinfunction "1_1") (pintype "passive"))
      (node (ref "U1") (pin "36") (pinfunction "GPIO33_36") (pintype "passive"))
      (node (ref "U2") (pin "5") (pinfunction "~{OCTW}_5") (pintype "output"))
    )
    (net (code "28") (name "/PWM_AH") (class "Default")
      (node (ref "U1") (pin "29") (pinfunction "GPIO0_29") (pintype "passive"))
      (node (ref "U2") (pin "17") (pinfunction "INH_A_17") (pintype "input"))
    )
    (net (code "29") (name "/PWM_AL") (class "Default")
      (node (ref "U1") (pin "28") (pinfunction "GPIO1_28") (pintype "passive"))
      (node (ref "U2") (pin "18") (pinfunction "INL_A_18") (pintype "input"))
    )
    (net (code "30") (name "/PWM_BH") (class "Default")
      (node (ref "U1") (pin "37") (pinfunction "GPIO2_37") (pintype "passive"))
      (node (ref "U2") (pin "19") (pinfunction "INH_B_19") (pintype "input"))
    )
    (net (code "31") (name "/PWM_BL") (class "Default")
      (node (ref "U1") (pin "38") (pinfunction "GPIO3_38") (pintype "passive"))
      (node (ref "U2") (pin "20") (pinfunction "INL_B_20") (pintype "input"))
    )
    (net (code "32") (name "/PWM_CH") (class "Default")
      (node (ref "U1") (pin "39") (pinfunction "GPIO4_39") (pintype "passive"))
      (node (ref "U2") (pin "21") (pinfunction "INH_C_21") (pintype "input"))
    )
    (net (code "33") (name "/PWM_CL") (class "Default")
      (node (ref "U1") (pin "40") (pinfunction "GPIO5_40") (pintype "passive"))
      (node (ref "U2") (pin "22") (pinfunction "INL_C_22") (pintype "input"))
    )
    (net (code "34") (name "/RE") (class "Default")
      (node (ref "U1") (pin "47") (pinfunction "GPIO12_47") (pintype "passive"))
      (node (ref "U6") (pin "2") (pinfunction "~{RE}_2") (pintype "passive"))
    )
    (net (code "35") (name "/RESET") (class "Default")
      (node (ref "R24") (pin "2") (pinfunction "2_2") (pintype "passive"))
      (node (ref "U1") (pin "3") (pinfunction "~{XRS}_3") (pintype "passive"))
    )
    (net (code "36") (name "/RX") (class "Default")
      (node (ref "U1") (pin "48") (pinfunction "GPIO28_48") (pintype "passive"))
      (node (ref "U6") (pin "1") (pinfunction "R_1") (pintype "passive"))
    )
    (net (code "37") (name "/SCLK") (class "Default")
      (node (ref "U1") (pin "24") (pinfunction "GPIO18_24") (pintype "passive"))
      (node (ref "U2") (pin "11") (pinfunction "SCLK_11") (pintype "input"))
      (node (ref "U8") (pin "1") (pinfunction "CLK_1") (pintype "passive"))
    )
    (net (code "38") (name "/SCS") (class "Default")
      (node (ref "U1") (pin "25") (pinfunction "GPIO19_25") (pintype "passive"))
      (node (ref "U2") (pin "8") (pinfunction "~{SCS}_8") (pintype "input"))
    )
    (net (code "39") (name "/SCS2") (class "Default")
      (node (ref "U1") (pin "19") (pinfunction "GPIO34_19") (pintype "passive"))
      (node (ref "U8") (pin "5") (pinfunction "~{CS}_5") (pintype "passive"))
    )
    (net (code "40") (name "/SDI") (class "Default")
      (node (ref "U1") (pin "27") (pinfunction "GPIO16_27") (pintype "passive"))
      (node (ref "U2") (pin "9") (pinfunction "SDI_9") (pintype "input"))
      (node (ref "U8") (pin "3") (pinfunction "SI_3") (pintype "passive"))
    )
    (net (code "41") (name "/SDO") (class "Default")
      (node (ref "U1") (pin "26") (pinfunction "GPIO17_26") (pintype "passive"))
      (node (ref "U2") (pin "10") (pinfunction "SDO_10") (pintype "output"))
      (node (ref "U8") (pin "4") (pinfunction "SO_4") (pintype "passive"))
    )
    (net (code "42") (name "/SH_A") (class "Default")
      (node (ref "C10") (pin "1") (pinfunction "1_1") (pintype "passive"))
      (node (ref "J16") (pin "1") (pinfunction "1_1") (pintype "passive"))
      (node (ref "Q1") (pin "S") (pinfunction "S_S") (pintype "passive"))
      (node (ref "Q2") (pin "D") (pinfunction "D_D") (pintype "passive"))
      (node (ref "R11") (pin "2") (pinfunction "2_2") (pintype "passive"))
      (node (ref "U2") (pin "46") (pinfunction "SH_A_46") (pintype "input"))
    )
    (net (code "43") (name "/SH_B") (class "Default")
      (node (ref "C11") (pin "1") (pinfunction "1_1") (pintype "passive"))
      (node (ref "J17") (pin "1") (pinfunction "1_1") (pintype "passive"))
      (node (ref "Q3") (pin "S") (pinfunction "S_S") (pintype "passive"))
      (node (ref "Q4") (pin "D") (pinfunction "D_D") (pintype "passive"))
      (node (ref "R12") (pin "2") (pinfunction "2_2") (pintype "passive"))
      (node (ref "U2") (pin "41") (pinfunction "SH_B_41") (pintype "input"))
    )
    (net (code "44") (name "/SH_C") (class "Default")
      (node (ref "C12") (pin "1") (pinfunction "1_1") (pintype "passive"))
      (node (ref "J18") (pin "1") (pinfunction "1_1") (pintype "passive"))
      (node (ref "Q5") (pin "S") (pinfunction "S_S") (pintype "passive"))
      (node (ref "Q6") (pin "D") (pinfunction "D_D") (pintype "passive"))
      (node (ref "R13") (pin "2") (pinfunction "2_2") (pintype "passive"))
      (node (ref "U2") (pin "36") (pinfunction "SH_C_36") (pintype "input"))
    )
    (net (code "45") (name "/SL_A") (class "Default")
      (node (ref "J20") (pin "2") (pinfunction "2_2") (pintype "passive"))
      (node (ref "Q2") (pin "S") (pinfunction "S_S") (pintype "passive"))
      (node (ref "R7") (pin "2") (pinfunction "2_2") (pintype "passive"))
      (node (ref "U2") (pin "44") (pinfunction "SL_A_44") (pintype "input"))
    )
    (net (code "46") (name "/SL_B") (class "Default")
      (node (ref "J22") (pin "2") (pinfunction "2_2") (pintype "passive"))
      (node (ref "Q4") (pin "S") (pinfunction "S_S") (pintype "passive"))
      (node (ref "R8") (pin "2") (pinfunction "2_2") (pintype "passive"))
      (node (ref "U2") (pin "39") (pinfunction "SL_B_39") (pintype "input"))
    )
    (net (code "47") (name "/SL_C") (class "Default")
      (node (ref "J24") (pin "2") (pinfunction "2_2") (pintype "passive"))
      (node (ref "Q6") (pin "S") (pinfunction "S_S") (pintype "passive"))
      (node (ref "R9") (pin "2") (pinfunction "2_2") (pintype "passive"))
      (node (ref "U2") (pin "34") (pinfunction "SL_C_34") (pintype "input"))
    )
    (net (code "48") (name "/TCK") (class "Default")
      (node (ref "J12") (pin "7") (pinfunction "7_7") (pintype "passive"))
      (node (ref "U1") (pin "23") (pinfunction "TCK_23") (pintype "passive"))
    )
    (net (code "49") (name "/TDI") (class "Default")
      (node (ref "J12") (pin "4") (pinfunction "4_4") (pintype "passive"))
      (node (ref "U1") (pin "20") (pinfunction "TDI_20") (pintype "passive"))
    )
    (net (code "50") (name "/TDO") (class "Default")
      (node (ref "J12") (pin "5") (pinfunction "5_5") (pintype "passive"))
      (node (ref "U1") (pin "22") (pinfunction "TDO_22") (pintype "passive"))
    )
    (net (code "51") (name "/TMS") (class "Default")
      (node (ref "J12") (pin "6") (pinfunction "6_6") (pintype "passive"))
      (node (ref "U1") (pin "21") (pinfunction "TMS_21") (pintype "passive"))
    )
    (net (code "52") (name "/TRST") (class "Default")
      (node (ref "J12") (pin "3") (pinfunction "3_3") (pintype "passive"))
      (node (ref "R48") (pin "1") (pinfunction "1_1") (pintype "passive"))
      (node (ref "U1") (pin "2") (pinfunction "~{TRST}_2") (pintype "passive"))
    )
    (net (code "53") (name "/TX") (class "Default")
      (node (ref "U1") (pin "1") (pinfunction "GPIO29_1") (pintype "passive"))
      (node (ref "U6") (pin "4") (pinfunction "D_4") (pintype "passive"))
    )
    (net (code "54") (name "/VA_FB") (class "Default")
      (node (ref "C16") (pin "2") (pinfunction "2_2") (pintype "passive"))
      (node (ref "R11") (pin "1") (pinfunction "1_1") (pintype "passive"))
      (node (ref "R14") (pin "2") (pinfunction "2_2") (pintype "passive"))
      (node (ref "U1") (pin "7") (pinfunction "ADCINA3_7") (pintype "passive"))
      (node (ref "U3") (pin "4") (pinfunction "IO_4") (pintype "passive"))
    )
    (net (code "55") (name "/VB_FB") (class "Default")
      (node (ref "C17") (pin "2") (pinfunction "2_2") (pintype "passive"))
      (node (ref "R12") (pin "1") (pinfunction "1_1") (pintype "passive"))
      (node (ref "R15") (pin "2") (pinfunction "2_2") (pintype "passive"))
      (node (ref "U1") (pin "8") (pinfunction "ADCINA1_8") (pintype "passive"))
      (node (ref "U3") (pin "3") (pinfunction "IO_3") (pintype "passive"))
    )
    (net (code "56") (name "/VC_FB") (class "Default")
      (node (ref "C18") (pin "2") (pinfunction "2_2") (pintype "passive"))
      (node (ref "R13") (pin "1") (pinfunction "1_1") (pintype "passive"))
      (node (ref "R16") (pin "2") (pinfunction "2_2") (pintype "passive"))
      (node (ref "U1") (pin "10") (pinfunction "ADCINA0_10") (pintype "passive"))
      (node (ref "U3") (pin "1") (pinfunction "IO_1") (pintype "passive"))
    )
    (net (code "57") (name "/Y") (class "Default")
      (node (ref "J13") (pin "6") (pinfunction "6_6") (pintype "passive"))
      (node (ref "R47") (pin "2") (pinfunction "2_2") (pintype "passive"))
      (node (ref "U6") (pin "6") (pinfunction "Y_6") (pintype "passive"))
    )
    (net (code "58") (name "/Z") (class "Default")
      (node (ref "J13") (pin "5") (pinfunction "5_5") (pintype "passive"))
      (node (ref "R47") (pin "1") (pinfunction "1_1") (pintype "passive"))
      (node (ref "U6") (pin "7") (pinfunction "Z_7") (pintype "passive"))
    )
    (net (code "59") (name "3.3V") (class "Default")
      (node (ref "C26") (pin "2") (pinfunction "2_2") (pintype "passive"))
      (node (ref "C31") (pin "1") (pinfunction "1_1") (pintype "passive"))
      (node (ref "C32") (pin "1") (pinfunction "1_1") (pintype "passive"))
      (node (ref "C34") (pin "2") (pinfunction "2_2") (pintype "passive"))
      (node (ref "C37") (pin "2") (pinfunction "2_2") (pintype "passive"))
      (node (ref "FB1") (pin "2") (pinfunction "2_2") (pintype "passive"))
      (node (ref "FB2") (pin "2") (pinfunction "2_2") (pintype "passive"))
      (node (ref "J12") (pin "2") (pinfunction "2_2") (pintype "passive"))
      (node (ref "J13") (pin "2") (pinfunction "2_2") (pintype "passive"))
      (node (ref "R24") (pin "1") (pinfunction "1_1") (pintype "passive"))
      (node (ref "R26") (pin "2") (pinfunction "2_2") (pintype "passive"))
      (node (ref "R27") (pin "2") (pinfunction "2_2") (pintype "passive"))
      (node (ref "R36") (pin "2") (pinfunction "2_2") (pintype "passive"))
      (node (ref "R42") (pin "1") (pinfunction "1_1") (pintype "passive"))
      (node (ref "U2") (pin "24") (pinfunction "REF_24") (pintype "input"))
      (node (ref "U2") (pin "49") (pinfunction "VDD_SPI_49") (pintype "input"))
      (node (ref "U3") (pin "5") (pinfunction "VP_5") (pintype "passive"))
      (node (ref "U4") (pin "8") (pinfunction "V+_8") (pintype "passive"))
      (node (ref "U6") (pin "10") (pinfunction "VCC_10") (pintype "passive"))
      (node (ref "U8") (pin "6") (pinfunction "VCC_6") (pintype "passive"))
    )
    (net (code "60") (name "16V") (class "Default")
      (node (ref "C14") (pin "2") (pinfunction "2_2") (pintype "passive"))
      (node (ref "C15") (pin "1") (pinfunction "1_1") (pintype "passive"))
      (node (ref "C20") (pin "2") (pinfunction "2_2") (pintype "passive"))
      (node (ref "C39") (pin "1") (pintype "passive"))
      (node (ref "C4") (pin "1") (pinfunction "1_1") (pintype "passive"))
      (node (ref "C40") (pin "1") (pintype "passive"))
      (node (ref "C5") (pin "1") (pinfunction "1_1") (pintype "passive"))
      (node (ref "C6") (pin "1") (pinfunction "1_1") (pintype "passive"))
      (node (ref "J19") (pin "1") (pinfunction "1_1") (pintype "passive"))
      (node (ref "Q1") (pin "D") (pinfunction "D_D") (pintype "passive"))
      (node (ref "Q3") (pin "D") (pinfunction "D_D") (pintype "passive"))
      (node (ref "Q5") (pin "D") (pinfunction "D_D") (pintype "passive"))
      (node (ref "R17") (pin "2") (pinfunction "2_2") (pintype "passive"))
      (node (ref "R18") (pin "2") (pinfunction "2_2") (pintype "passive"))
      (node (ref "R19") (pin "2") (pinfunction "2_2") (pintype "passive"))
      (node (ref "R41") (pin "1") (pinfunction "1_1") (pintype "passive"))
      (node (ref "U2") (pin "29") (pinfunction "PVDD1_29") (pintype "power_in"))
    )
    (net (code "61") (name "GND") (class "Default")
      (node (ref "C1") (pin "1") (pinfunction "1_1") (pintype "passive"))
      (node (ref "C14") (pin "1") (pinfunction "1_1") (pintype "passive"))
      (node (ref "C15") (pin "2") (pinfunction "2_2") (pintype "passive"))
      (node (ref "C16") (pin "1") (pinfunction "1_1") (pintype "passive"))
      (node (ref "C17") (pin "1") (pinfunction "1_1") (pintype "passive"))
      (node (ref "C18") (pin "1") (pinfunction "1_1") (pintype "passive"))
      (node (ref "C2") (pin "1") (pinfunction "1_1") (pintype "passive"))
      (node (ref "C20") (pin "1") (pinfunction "1_1") (pintype "passive"))
      (node (ref "C21") (pin "1") (pinfunction "1_1") (pintype "passive"))
      (node (ref "C22") (pin "1") (pinfunction "1_1") (pintype "passive"))
      (node (ref "C23") (pin "1") (pinfunction "1_1") (pintype "passive"))
      (node (ref "C24") (pin "1") (pinfunction "1_1") (pintype "passive"))
      (node (ref "C25") (pin "1") (pinfunction "1_1") (pintype "passive"))
      (node (ref "C26") (pin "1") (pinfunction "1_1") (pintype "passive"))
      (node (ref "C27") (pin "1") (pinfunction "1_1") (pintype "passive"))
      (node (ref "C28") (pin "1") (pinfunction "1_1") (pintype "passive"))
      (node (ref "C29") (pin "1") (pinfunction "1_1") (pintype "passive"))
      (node (ref "C3") (pin "1") (pinfunction "1_1") (pintype "passive"))
      (node (ref "C30") (pin "1") (pinfunction "1_1") (pintype "passive"))
      (node (ref "C31") (pin "2") (pinfunction "2_2") (pintype "passive"))
      (node (ref "C32") (pin "2") (pinfunction "2_2") (pintype "passive"))
      (node (ref "C34") (pin "1") (pinfunction "1_1") (pintype "passive"))
      (node (ref "C35") (pin "1") (pinfunction "1_1") (pintype "passive"))
      (node (ref "C37") (pin "1") (pinfunction "1_1") (pintype "passive"))
      (node (ref "C39") (pin "2") (pintype "passive"))
      (node (ref "C4") (pin "2") (pinfunction "2_2") (pintype "passive"))
      (node (ref "C40") (pin "2") (pintype "passive"))
      (node (ref "C5") (pin "2") (pinfunction "2_2") (pintype "passive"))
      (node (ref "C6") (pin "2") (pinfunction "2_2") (pintype "passive"))
      (node (ref "D1") (pin "2") (pinfunction "2_2") (pintype "passive"))
      (node (ref "D2") (pin "2") (pinfunction "K_2") (pintype "passive"))
      (node (ref "D3") (pin "2") (pinfunction "K_2") (pintype "passive"))
      (node (ref "J12") (pin "1") (pinfunction "1_1") (pintype "passive"))
      (node (ref "J12") (pin "8") (pinfunction "8_8") (pintype "passive"))
      (node (ref "J13") (pin "1") (pinfunction "1_1") (pintype "passive"))
      (node (ref "J21") (pin "2") (pinfunction "2_2") (pintype "passive"))
      (node (ref "J23") (pin "2") (pinfunction "2_2") (pintype "passive"))
      (node (ref "J25") (pin "2") (pinfunction "2_2") (pintype "passive"))
      (node (ref "Q7") (pin "S") (pinfunction "S_S") (pintype "passive"))
      (node (ref "R10") (pin "1") (pinfunction "1_1") (pintype "passive"))
      (node (ref "R14") (pin "1") (pinfunction "1_1") (pintype "passive"))
      (node (ref "R15") (pin "1") (pinfunction "1_1") (pintype "passive"))
      (node (ref "R16") (pin "1") (pinfunction "1_1") (pintype "passive"))
      (node (ref "R20") (pin "1") (pinfunction "1_1") (pintype "passive"))
      (node (ref "R25") (pin "1") (pinfunction "1_1") (pintype "passive"))
      (node (ref "R28") (pin "1") (pinfunction "1_1") (pintype "passive"))
      (node (ref "R37") (pin "1") (pinfunction "1_1") (pintype "passive"))
      (node (ref "R38") (pin "1") (pinfunction "1_1") (pintype "passive"))
      (node (ref "R48") (pin "2") (pinfunction "2_2") (pintype "passive"))
      (node (ref "R7") (pin "1") (pinfunction "1_1") (pintype "passive"))
      (node (ref "R8") (pin "1") (pinfunction "1_1") (pintype "passive"))
      (node (ref "R9") (pin "1") (pinfunction "1_1") (pintype "passive"))
      (node (ref "U1") (pin "12") (pinfunction "VSSA_12") (pintype "passive"))
      (node (ref "U1") (pin "30") (pinfunction "TEST_30") (pintype "passive"))
      (node (ref "U1") (pin "33") (pinfunction "VSS1_33") (pintype "passive"))
      (node (ref "U1") (pin "34") (pinfunction "~{VREGENZ}_34") (pintype "passive"))
      (node (ref "U1") (pin "44") (pinfunction "VSS2_44") (pintype "passive"))
      (node (ref "U2") (pin "28") (pinfunction "AGND_28") (pintype "power_in"))
      (node (ref "U2") (pin "57") (pinfunction "PWPD_57") (pintype "power_in"))
      (node (ref "U3") (pin "2") (pinfunction "VN_2") (pintype "passive"))
      (node (ref "U4") (pin "4") (pinfunction "V-_4") (pintype "passive"))
      (node (ref "U6") (pin "5") (pinfunction "GND_5") (pintype "passive"))
      (node (ref "U8") (pin "2") (pinfunction "GND_2") (pintype "passive"))
    )
    (net (code "62") (name "Net-(C21-Pad2)") (class "Default")
      (node (ref "C21") (pin "2") (pinfunction "2_2") (pintype "passive"))
      (node (ref "R18") (pin "1") (pinfunction "1_1") (pintype "passive"))
    )
    (net (code "63") (name "Net-(D1-Pad1)") (class "Default")
      (node (ref "D1") (pin "1") (pinfunction "1_1") (pintype "passive"))
      (node (ref "Q7") (pin "G") (pinfunction "G_G") (pintype "passive"))
      (node (ref "R17") (pin "1") (pinfunction "1_1") (pintype "passive"))
    )
    (net (code "64") (name "Net-(D2-A)") (class "Default")
      (node (ref "D2") (pin "1") (pinfunction "A_1") (pintype "passive"))
      (node (ref "R41") (pin "2") (pinfunction "2_2") (pintype "passive"))
    )
    (net (code "65") (name "Net-(D3-A)") (class "Default")
      (node (ref "D3") (pin "1") (pinfunction "A_1") (pintype "passive"))
      (node (ref "R42") (pin "2") (pinfunction "2_2") (pintype "passive"))
    )
    (net (code "66") (name "Net-(Q1-PadG)") (class "Default")
      (node (ref "Q1") (pin "G") (pinfunction "G_G") (pintype "passive"))
      (node (ref "R1") (pin "2") (pinfunction "2_2") (pintype "passive"))
    )
    (net (code "67") (name "Net-(Q2-PadG)") (class "Default")
      (node (ref "Q2") (pin "G") (pinfunction "G_G") (pintype "passive"))
      (node (ref "R2") (pin "2") (pinfunction "2_2") (pintype "passive"))
    )
    (net (code "68") (name "Net-(Q3-PadG)") (class "Default")
      (node (ref "Q3") (pin "G") (pinfunction "G_G") (pintype "passive"))
      (node (ref "R3") (pin "2") (pinfunction "2_2") (pintype "passive"))
    )
    (net (code "69") (name "Net-(Q4-PadG)") (class "Default")
      (node (ref "Q4") (pin "G") (pinfunction "G_G") (pintype "passive"))
      (node (ref "R4") (pin "2") (pinfunction "2_2") (pintype "passive"))
    )
    (net (code "70") (name "Net-(Q5-PadG)") (class "Default")
      (node (ref "Q5") (pin "G") (pinfunction "G_G") (pintype "passive"))
      (node (ref "R5") (pin "2") (pinfunction "2_2") (pintype "passive"))
    )
    (net (code "71") (name "Net-(Q6-PadG)") (class "Default")
      (node (ref "Q6") (pin "G") (pinfunction "G_G") (pintype "passive"))
      (node (ref "R6") (pin "2") (pinfunction "2_2") (pintype "passive"))
    )
    (net (code "72") (name "Net-(U1-VDD1)") (class "Default")
      (node (ref "C28") (pin "2") (pinfunction "2_2") (pintype "passive"))
      (node (ref "U1") (pin "32") (pinfunction "VDD1_32") (pintype "passive"))
    )
    (net (code "73") (name "Net-(U1-VDD2)") (class "Default")
      (node (ref "C29") (pin "2") (pinfunction "2_2") (pintype "passive"))
      (node (ref "U1") (pin "43") (pinfunction "VDD2_43") (pintype "passive"))
    )
    (net (code "74") (name "Net-(U1-VDDA)") (class "Default")
      (node (ref "C27") (pin "2") (pinfunction "2_2") (pintype "passive"))
      (node (ref "FB1") (pin "1") (pinfunction "1_1") (pintype "passive"))
      (node (ref "U1") (pin "11") (pinfunction "VDDA_11") (pintype "passive"))
    )
    (net (code "75") (name "Net-(U1-VDDIO)") (class "Default")
      (node (ref "C30") (pin "2") (pinfunction "2_2") (pintype "passive"))
      (node (ref "FB2") (pin "1") (pinfunction "1_1") (pintype "passive"))
      (node (ref "U1") (pin "35") (pinfunction "VDDIO_35") (pintype "passive"))
    )
    (net (code "76") (name "Net-(U2-AVDD)") (class "Default")
      (node (ref "C1") (pin "2") (pinfunction "2_2") (pintype "passive"))
      (node (ref "U2") (pin "27") (pinfunction "AVDD_27") (pintype "power_in"))
    )
    (net (code "77") (name "Net-(U2-BST_A)") (class "Default")
      (node (ref "C10") (pin "2") (pinfunction "2_2") (pintype "passive"))
      (node (ref "U2") (pin "48") (pinfunction "BST_A_48") (pintype "power_in"))
    )
    (net (code "78") (name "Net-(U2-BST_B)") (class "Default")
      (node (ref "C11") (pin "2") (pinfunction "2_2") (pintype "passive"))
      (node (ref "U2") (pin "43") (pinfunction "BST_B_43") (pintype "power_in"))
    )
    (net (code "79") (name "Net-(U2-BST_C)") (class "Default")
      (node (ref "C12") (pin "2") (pinfunction "2_2") (pintype "passive"))
      (node (ref "U2") (pin "38") (pinfunction "BST_C_38") (pintype "power_in"))
    )
    (net (code "80") (name "Net-(U2-CP1)") (class "Default")
      (node (ref "C13") (pin "1") (pinfunction "1_1") (pintype "passive"))
      (node (ref "U2") (pin "14") (pinfunction "CP1_14") (pintype "power_in"))
    )
    (net (code "81") (name "Net-(U2-CP2)") (class "Default")
      (node (ref "C13") (pin "2") (pinfunction "2_2") (pintype "passive"))
      (node (ref "U2") (pin "15") (pinfunction "CP2_15") (pintype "power_in"))
    )
    (net (code "82") (name "Net-(U2-DTC)") (class "Default")
      (node (ref "R28") (pin "2") (pinfunction "2_2") (pintype "passive"))
      (node (ref "U2") (pin "7") (pinfunction "DTC_7") (pintype "input"))
    )
    (net (code "83") (name "Net-(U2-DVDD)") (class "Default")
      (node (ref "C2") (pin "2") (pinfunction "2_2") (pintype "passive"))
      (node (ref "U2") (pin "23") (pinfunction "DVDD_23") (pintype "power_in"))
    )
    (net (code "84") (name "Net-(U2-EN_BUCK)") (class "Default")
      (node (ref "R38") (pin "2") (pinfunction "2_2") (pintype "passive"))
      (node (ref "U2") (pin "55") (pinfunction "EN_BUCK_55") (pintype "input"))
    )
    (net (code "85") (name "Net-(U2-GVDD)") (class "Default")
      (node (ref "C3") (pin "2") (pinfunction "2_2") (pintype "passive"))
      (node (ref "U2") (pin "13") (pinfunction "GVDD_13") (pintype "power_in"))
    )
    (net (code "86") (name "Net-(U4-IN_A+)") (class "Default")
      (node (ref "R33") (pin "1") (pinfunction "1_1") (pintype "passive"))
      (node (ref "R35") (pin "1") (pinfunction "1_1") (pintype "passive"))
      (node (ref "U4") (pin "3") (pinfunction "IN_A+_3") (pintype "passive"))
    )
    (net (code "87") (name "Net-(U4-IN_A-)") (class "Default")
      (node (ref "R32") (pin "1") (pinfunction "1_1") (pintype "passive"))
      (node (ref "R34") (pin "2") (pinfunction "2_2") (pintype "passive"))
      (node (ref "U4") (pin "2") (pinfunction "IN_A-_2") (pintype "passive"))
    )
    (net (code "88") (name "Net-(U4-IN_B+)") (class "Default")
      (node (ref "R36") (pin "1") (pinfunction "1_1") (pintype "passive"))
      (node (ref "R37") (pin "2") (pinfunction "2_2") (pintype "passive"))
      (node (ref "U4") (pin "5") (pinfunction "IN_B+_5") (pintype "passive"))
    )
    (net (code "89") (name "Net-(U4-IN_B-)") (class "Default")
      (node (ref "C35") (pin "2") (pinfunction "2_2") (pintype "passive"))
      (node (ref "R35") (pin "2") (pinfunction "2_2") (pintype "passive"))
      (node (ref "U4") (pin "6") (pinfunction "IN_B-_6") (pintype "passive"))
      (node (ref "U4") (pin "7") (pinfunction "OUT_B_7") (pintype "passive"))
    )
    (net (code "90") (name "unconnected-(U1-ADCINA2-Pad9)") (class "Default")
      (node (ref "U1") (pin "9") (pinfunction "ADCINA2_9") (pintype "passive"))
    )
    (net (code "91") (name "unconnected-(U1-ADCINA4-Pad5)") (class "Default")
      (node (ref "U1") (pin "5") (pinfunction "ADCINA4_5") (pintype "passive"))
    )
    (net (code "92") (name "unconnected-(U1-ADCINB2-Pad14)") (class "Default")
      (node (ref "U1") (pin "14") (pinfunction "ADCINB2_14") (pintype "passive"))
    )
    (net (code "93") (name "unconnected-(U1-ADCINB4-Pad16)") (class "Default")
      (node (ref "U1") (pin "16") (pinfunction "ADCINB4_16") (pintype "passive"))
    )
    (net (code "94") (name "unconnected-(U1-ADCINB6-Pad17)") (class "Default")
      (node (ref "U1") (pin "17") (pinfunction "ADCINB6_17") (pintype "passive"))
    )
    (net (code "95") (name "unconnected-(U1-X1-Pad45)") (class "Default")
      (node (ref "U1") (pin "45") (pinfunction "X1_45") (pintype "passive"))
    )
    (net (code "96") (name "unconnected-(U1-X2-Pad46)") (class "Default")
      (node (ref "U1") (pin "46") (pinfunction "X2_46") (pintype "passive"))
    )
    (net (code "97") (name "unconnected-(U2-BST_BK-Pad52)") (class "Default")
      (node (ref "U2") (pin "52") (pinfunction "BST_BK_52") (pintype "power_in"))
    )
    (net (code "98") (name "unconnected-(U2-COMP-Pad2)") (class "Default")
      (node (ref "U2") (pin "2") (pinfunction "COMP_2") (pintype "output"))
    )
    (net (code "99") (name "unconnected-(U2-PH-Pad50)") (class "Default")
      (node (ref "U2") (pin "50") (pinfunction "PH_50") (pintype "output"))
    )
    (net (code "100") (name "unconnected-(U2-PH-Pad51)") (class "Default")
      (node (ref "U2") (pin "51") (pinfunction "PH_51") (pintype "output"))
    )
    (net (code "101") (name "unconnected-(U2-PVDD2-Pad53)") (class "Default")
      (node (ref "U2") (pin "53") (pinfunction "PVDD2_53") (pintype "power_in"))
    )
    (net (code "102") (name "unconnected-(U2-PVDD2-Pad54)") (class "Default")
      (node (ref "U2") (pin "54") (pinfunction "PVDD2_54") (pintype "power_in"))
    )
    (net (code "103") (name "unconnected-(U2-PWRGD-Pad4)") (class "Default")
      (node (ref "U2") (pin "4") (pinfunction "PWRGD_4") (pintype "output"))
    )
    (net (code "104") (name "unconnected-(U2-RT_CLK-Pad1)") (class "Default")
      (node (ref "U2") (pin "1") (pinfunction "RT_CLK_1") (pintype "input"))
    )
    (net (code "105") (name "unconnected-(U2-SS_TR-Pad56)") (class "Default")
      (node (ref "U2") (pin "56") (pinfunction "SS_TR_56") (pintype "input"))
    )
    (net (code "106") (name "unconnected-(U2-VSENSE-Pad3)") (class "Default")
      (node (ref "U2") (pin "3") (pinfunction "VSENSE_3") (pintype "input"))
    )
  )
)
